# design.net
KiCad netlist of a schematic drawn in Altium Designer
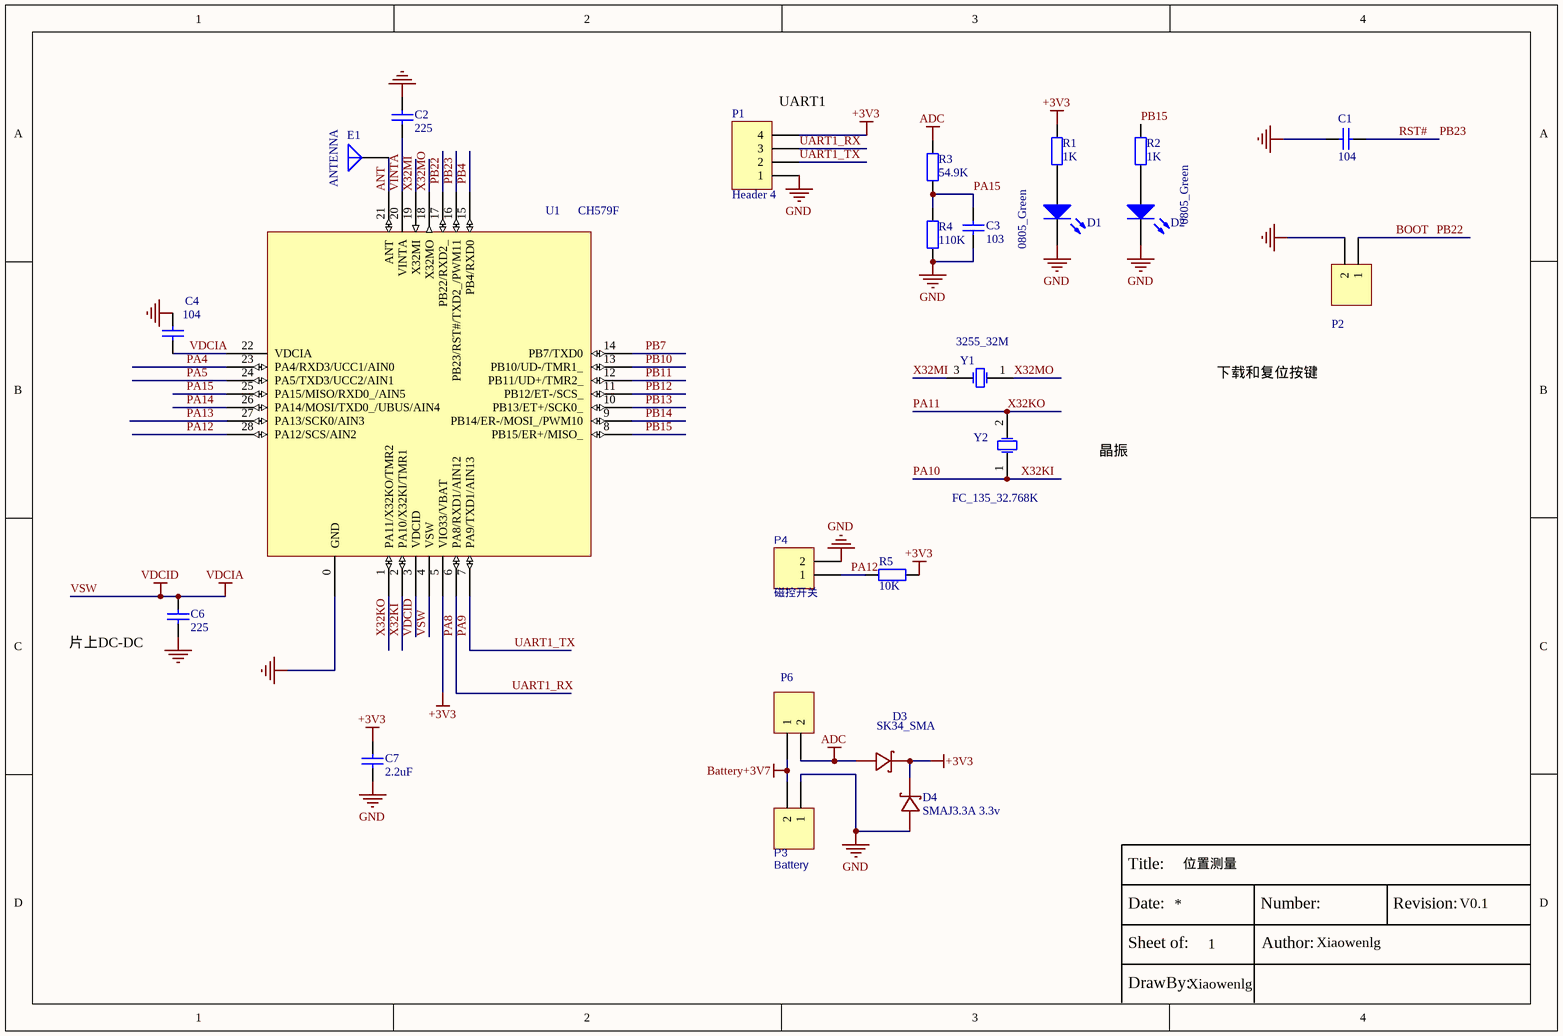
[diagram p0: 蓝牙传输.SchDoc]

(export (version "E")
  (design (tool "Eeschema 10.0.6"))
  (components
    (comp (ref "C1")
      (value "104")
      (footprint "C-RAD-0603")
      (description "无极性电容")
      (fields (field (name "Comment") "Cap") (field (name "PUBLISHER") "Altium Limited"))
      (libsource (lib "MYLibrary") (part "Cap"))
    )
    (comp (ref "C2")
      (value "225")
      (footprint "C-RAD-0603")
      (description "无极性电容")
      (fields (field (name "Comment") "Cap") (field (name "PUBLISHER") "Altium Limited"))
      (libsource (lib "MYLibrary") (part "Cap"))
    )
    (comp (ref "C3")
      (value "103")
      (footprint "C-RAD-0603")
      (description "无极性电容")
      (fields (field (name "Comment") "Cap") (field (name "PUBLISHER") "Altium Limited"))
      (libsource (lib "MYLibrary") (part "Cap"))
    )
    (comp (ref "C4")
      (value "104")
      (footprint "C-RAD-0603")
      (description "无极性电容")
      (fields (field (name "Comment") "Cap") (field (name "PUBLISHER") "Altium Limited"))
      (libsource (lib "MYLibrary") (part "Cap"))
    )
    (comp (ref "C6")
      (value "225")
      (footprint "C-RAD-0603")
      (description "无极性电容")
      (fields (field (name "Comment") "Cap") (field (name "PUBLISHER") "Altium Limited"))
      (libsource (lib "MYLibrary") (part "Cap"))
    )
    (comp (ref "C7")
      (value "2.2uF")
      (footprint "C-RAD-0805")
      (description "无极性电容")
      (fields (field (name "Comment") "Cap") (field (name "PUBLISHER") "Altium Limited"))
      (libsource (lib "MYLibrary") (part "Cap"))
    )
    (comp (ref "D1")
      (value "0805_Green")
      (footprint "LED_0805")
      (description "发光二极管")
      (fields (field (name "Comment") "LED0") (field (name "PUBLISHER") "Altium Limited"))
      (libsource (lib "Fszhang") (part "LED0"))
    )
    (comp (ref "D2")
      (value "0805_Green")
      (footprint "LED_0805")
      (description "发光二极管")
      (fields (field (name "Comment") "LED0") (field (name "PUBLISHER") "Altium Limited"))
      (libsource (lib "Fszhang") (part "LED0"))
    )
    (comp (ref "D3")
      (value "SK34_SMA")
      (footprint "SMA_L4.3-W2.6-LS5.2-RD")
      (description "快恢复二极管")
      (fields (field (name "BOM_MANUFACTURER PART") "SK34") (field (name "BOM_SUPPLIER PART") "C65008"))
      (libsource (lib "MYLibrary") (part "SK34_C65008"))
    )
    (comp (ref "D4")
      (value "SMAJ3.3A 3.3v")
      (footprint "SMA_L4.3-W2.6-LS5.2-RD")
      (description "TVS二极管")
      (fields (field (name "BOM_MANUFACTURER PART") "SK34") (field (name "BOM_SUPPLIER PART") "C65008"))
      (libsource (lib "") (part "SK34_C65008_1"))
    )
    (comp (ref "E1")
      (value "ANTENNA")
      (footprint "ANT-F-1-2.4G-1.6")
      (description "Generic Antenna")
      (libsource (lib "MYLibrary") (part "ANTENNA"))
    )
    (comp (ref "P1")
      (value "Header 4")
      (footprint "HDR1X4")
      (description "Header, 4-Pin")
      (fields (field (name "PUBLISHER") "Altium Limited"))
      (libsource (lib "Miscellaneous Connectors") (part "Header 4"))
    )
    (comp (ref "P2")
      (value "Header 2")
      (footprint "HDR2X1_A")
      (description "接插件")
      (fields (field (name "PUBLISHER") "Altium Limited"))
      (libsource (lib "") (part "Header 2_1"))
    )
    (comp (ref "P3")
      (value "Battery")
      (footprint "XH2.54")
      (description "接插件")
      (fields (field (name "PUBLISHER") "Altium Limited"))
      (libsource (lib "Fszhang") (part "Header 2"))
    )
    (comp (ref "P4")
      (value "磁控开关")
      (footprint "XH2.54")
      (description "接插件")
      (fields (field (name "PUBLISHER") "Altium Limited"))
      (libsource (lib "") (part "Header 2_1"))
    )
    (comp (ref "P6")
      (value "Header 2")
      (footprint "HDR2X1_A")
      (description "接插件")
      (fields (field (name "PUBLISHER") "Altium Limited"))
      (libsource (lib "MYLibrary") (part "Header 2"))
    )
    (comp (ref "R1")
      (value "1K")
      (footprint "0805-1")
      (description "贴片电阻")
      (fields (field (name "PUBLISHER") "Altium Limited"))
      (libsource (lib "Fszhang") (part "Res1"))
    )
    (comp (ref "R2")
      (value "1K")
      (footprint "0805-1")
      (description "贴片电阻")
      (fields (field (name "PUBLISHER") "Altium Limited"))
      (libsource (lib "Fszhang") (part "Res1"))
    )
    (comp (ref "R3")
      (value "54.9K")
      (footprint "0805-1")
      (description "贴片电阻")
      (fields (field (name "PUBLISHER") "Altium Limited"))
      (libsource (lib "Fszhang") (part "Res1"))
    )
    (comp (ref "R4")
      (value "110K")
      (footprint "0805-1")
      (description "贴片电阻")
      (fields (field (name "PUBLISHER") "Altium Limited"))
      (libsource (lib "Fszhang") (part "Res1"))
    )
    (comp (ref "R5")
      (value "10K")
      (footprint "0805-1")
      (description "贴片电阻")
      (fields (field (name "PUBLISHER") "Altium Limited"))
      (libsource (lib "") (part "Res1_1"))
    )
    (comp (ref "U1")
      (value "CH579F")
      (footprint "QFN28_4X4")
      (description "MCU+BLE")
      (libsource (lib "altium-import") (part "root_0_CH579F_"))
    )
    (comp (ref "Y1")
      (value "3255_32M")
      (footprint "3225")
      (description "Crystal Oscillator(晶振)")
      (fields (field (name "Comment") "32M") (field (name "PUBLISHER") "Altium Limited"))
      (libsource (lib "") (part "XTAL_1"))
    )
    (comp (ref "Y2")
      (value "FC_135_32.768K")
      (footprint "fc-135")
      (description "Crystal Oscillator(晶振)")
      (fields (field (name "Comment") "32.768K") (field (name "PUBLISHER") "Altium Limited"))
      (libsource (lib "*") (part "XTAL"))
    )
  )
  (nets
    (net (code "1") (name "+3V3") (class "Default")
      (node (ref "C7") (pin "2") (pinfunction "2_2") (pintype "passive"))
      (node (ref "D3") (pin "1") (pinfunction "K_1") (pintype "passive"))
      (node (ref "D4") (pin "1") (pinfunction "K_1") (pintype "passive"))
      (node (ref "P1") (pin "4") (pinfunction "4_4") (pintype "passive"))
      (node (ref "R1") (pin "2") (pinfunction "2_2") (pintype "passive"))
      (node (ref "R5") (pin "1") (pinfunction "1_1") (pintype "passive"))
      (node (ref "U1") (pin "5") (pinfunction "VIO33/VBAT_5") (pintype "power_in"))
    )
    (net (code "2") (name "/ANT") (class "Default")
      (node (ref "E1") (pin "1") (pinfunction "A_1") (pintype "passive"))
      (node (ref "U1") (pin "21") (pinfunction "ANT_21") (pintype "bidirectional"))
    )
    (net (code "3") (name "/BOOT") (class "Default")
      (node (ref "P2") (pin "1") (pinfunction "1_1") (pintype "passive"))
      (node (ref "U1") (pin "17") (pinfunction "PB22/RXD2__17") (pintype "bidirectional"))
    )
    (net (code "4") (name "/PA4") (class "Default")
      (node (ref "U1") (pin "23") (pinfunction "PA4/RXD3/UCC1/AIN0_23") (pintype "bidirectional"))
    )
    (net (code "5") (name "/PA5") (class "Default")
      (node (ref "U1") (pin "24") (pinfunction "PA5/TXD3/UCC2/AIN1_24") (pintype "bidirectional"))
    )
    (net (code "6") (name "/PA8") (class "Default")
      (node (ref "P1") (pin "3") (pinfunction "3_3") (pintype "passive"))
      (node (ref "U1") (pin "6") (pinfunction "PA8/RXD1/AIN12_6") (pintype "bidirectional"))
    )
    (net (code "7") (name "/PA9") (class "Default")
      (node (ref "P1") (pin "2") (pinfunction "2_2") (pintype "passive"))
      (node (ref "U1") (pin "7") (pinfunction "PA9/TXD1/AIN13_7") (pintype "bidirectional"))
    )
    (net (code "8") (name "/PA10") (class "Default")
      (node (ref "U1") (pin "2") (pinfunction "PA10/X32KI/TMR1_2") (pintype "bidirectional"))
      (node (ref "Y2") (pin "1") (pinfunction "OSC1_1") (pintype "passive"))
    )
    (net (code "9") (name "/PA11") (class "Default")
      (node (ref "U1") (pin "1") (pinfunction "PA11/X32KO/TMR2_1") (pintype "bidirectional"))
      (node (ref "Y2") (pin "2") (pinfunction "OSC2_2") (pintype "passive"))
    )
    (net (code "10") (name "/PA12") (class "Default")
      (node (ref "P4") (pin "1") (pinfunction "1_1") (pintype "passive"))
      (node (ref "R5") (pin "2") (pinfunction "2_2") (pintype "passive"))
      (node (ref "U1") (pin "28") (pinfunction "PA12/SCS/AIN2_28") (pintype "bidirectional"))
    )
    (net (code "11") (name "/PA13") (class "Default")
      (node (ref "U1") (pin "27") (pinfunction "PA13/SCK0/AIN3_27") (pintype "bidirectional"))
    )
    (net (code "12") (name "/PA14") (class "Default")
      (node (ref "U1") (pin "26") (pinfunction "PA14/MOSI/TXD0_/UBUS/AIN4_26") (pintype "bidirectional"))
    )
    (net (code "13") (name "/PA15") (class "Default")
      (node (ref "C3") (pin "2") (pinfunction "2_2") (pintype "passive"))
      (node (ref "R3") (pin "1") (pinfunction "1_1") (pintype "passive"))
      (node (ref "R4") (pin "2") (pinfunction "2_2") (pintype "passive"))
      (node (ref "U1") (pin "25") (pinfunction "PA15/MISO/RXD0_/AIN5_25") (pintype "bidirectional"))
    )
    (net (code "14") (name "/PB4") (class "Default")
      (node (ref "U1") (pin "15") (pinfunction "PB4/RXD0_15") (pintype "bidirectional"))
    )
    (net (code "15") (name "/PB7") (class "Default")
      (node (ref "U1") (pin "14") (pinfunction "PB7/TXD0_14") (pintype "bidirectional"))
    )
    (net (code "16") (name "/PB10") (class "Default")
      (node (ref "U1") (pin "13") (pinfunction "PB10/UD-/TMR1__13") (pintype "bidirectional"))
    )
    (net (code "17") (name "/PB11") (class "Default")
      (node (ref "U1") (pin "12") (pinfunction "PB11/UD+/TMR2__12") (pintype "bidirectional"))
    )
    (net (code "18") (name "/PB12") (class "Default")
      (node (ref "U1") (pin "11") (pinfunction "PB12/ET-/SCS__11") (pintype "bidirectional"))
    )
    (net (code "19") (name "/PB13") (class "Default")
      (node (ref "U1") (pin "10") (pinfunction "PB13/ET+/SCK0__10") (pintype "bidirectional"))
    )
    (net (code "20") (name "/PB14") (class "Default")
      (node (ref "U1") (pin "9") (pinfunction "PB14/ER-/MOSI_/PWM10_9") (pintype "bidirectional"))
    )
    (net (code "21") (name "/PB15") (class "Default")
      (node (ref "R2") (pin "2") (pinfunction "2_2") (pintype "passive"))
      (node (ref "U1") (pin "8") (pinfunction "PB15/ER+/MISO__8") (pintype "bidirectional"))
    )
    (net (code "22") (name "/PB23") (class "Default")
      (node (ref "C1") (pin "1") (pinfunction "1_1") (pintype "passive"))
      (node (ref "U1") (pin "16") (pinfunction "PB23/RST#/TXD2_/PWM11_16") (pintype "bidirectional"))
    )
    (net (code "23") (name "/VINTA") (class "Default")
      (node (ref "C2") (pin "1") (pinfunction "1_1") (pintype "passive"))
      (node (ref "U1") (pin "20") (pinfunction "VINTA_20") (pintype "power_in"))
    )
    (net (code "24") (name "/X32MI") (class "Default")
      (node (ref "U1") (pin "19") (pinfunction "X32MI_19") (pintype "input"))
      (node (ref "Y1") (pin "3") (pinfunction "OSC2_3") (pintype "passive"))
    )
    (net (code "25") (name "/X32MO") (class "Default")
      (node (ref "U1") (pin "18") (pinfunction "X32MO_18") (pintype "output"))
      (node (ref "Y1") (pin "1") (pinfunction "OSC1_1") (pintype "passive"))
    )
    (net (code "26") (name "ADC") (class "Default")
      (node (ref "D3") (pin "2") (pinfunction "A_2") (pintype "passive"))
      (node (ref "P6") (pin "2") (pinfunction "2_2") (pintype "passive"))
      (node (ref "R3") (pin "2") (pinfunction "2_2") (pintype "passive"))
    )
    (net (code "27") (name "Battery+3V7") (class "Default")
      (node (ref "P3") (pin "2") (pinfunction "2_2") (pintype "passive"))
      (node (ref "P6") (pin "1") (pinfunction "1_1") (pintype "passive"))
    )
    (net (code "28") (name "GND") (class "Default")
      (node (ref "C1") (pin "2") (pinfunction "2_2") (pintype "passive"))
      (node (ref "C2") (pin "2") (pinfunction "2_2") (pintype "passive"))
      (node (ref "C3") (pin "1") (pinfunction "1_1") (pintype "passive"))
      (node (ref "C4") (pin "2") (pinfunction "2_2") (pintype "passive"))
      (node (ref "C6") (pin "1") (pinfunction "1_1") (pintype "passive"))
      (node (ref "C7") (pin "1") (pinfunction "1_1") (pintype "passive"))
      (node (ref "D1") (pin "2") (pinfunction "K_2") (pintype "passive"))
      (node (ref "D2") (pin "2") (pinfunction "K_2") (pintype "passive"))
      (node (ref "D4") (pin "2") (pinfunction "A_2") (pintype "passive"))
      (node (ref "P1") (pin "1") (pinfunction "1_1") (pintype "passive"))
      (node (ref "P2") (pin "2") (pinfunction "2_2") (pintype "passive"))
      (node (ref "P3") (pin "1") (pinfunction "1_1") (pintype "passive"))
      (node (ref "P4") (pin "2") (pinfunction "2_2") (pintype "passive"))
      (node (ref "R4") (pin "1") (pinfunction "1_1") (pintype "passive"))
      (node (ref "U1") (pin "0") (pinfunction "GND_0") (pintype "power_in"))
    )
    (net (code "29") (name "Net-(D1-A)") (class "Default")
      (node (ref "D1") (pin "1") (pinfunction "A_1") (pintype "passive"))
      (node (ref "R1") (pin "1") (pinfunction "1_1") (pintype "passive"))
    )
    (net (code "30") (name "Net-(D2-A)") (class "Default")
      (node (ref "D2") (pin "1") (pinfunction "A_1") (pintype "passive"))
      (node (ref "R2") (pin "1") (pinfunction "1_1") (pintype "passive"))
    )
    (net (code "31") (name "VDCIA") (class "Default")
      (node (ref "C4") (pin "1") (pinfunction "1_1") (pintype "passive"))
      (node (ref "C6") (pin "2") (pinfunction "2_2") (pintype "passive"))
      (node (ref "U1") (pin "22") (pinfunction "VDCIA_22") (pintype "power_in"))
      (node (ref "U1") (pin "3") (pinfunction "VDCID_3") (pintype "power_in"))
      (node (ref "U1") (pin "4") (pinfunction "VSW_4") (pintype "power_in"))
    )
  )
)
